# mc33063a-led-cc-driver-mk-1_0.net
KiCad netlist of a schematic drawn in EAGLE
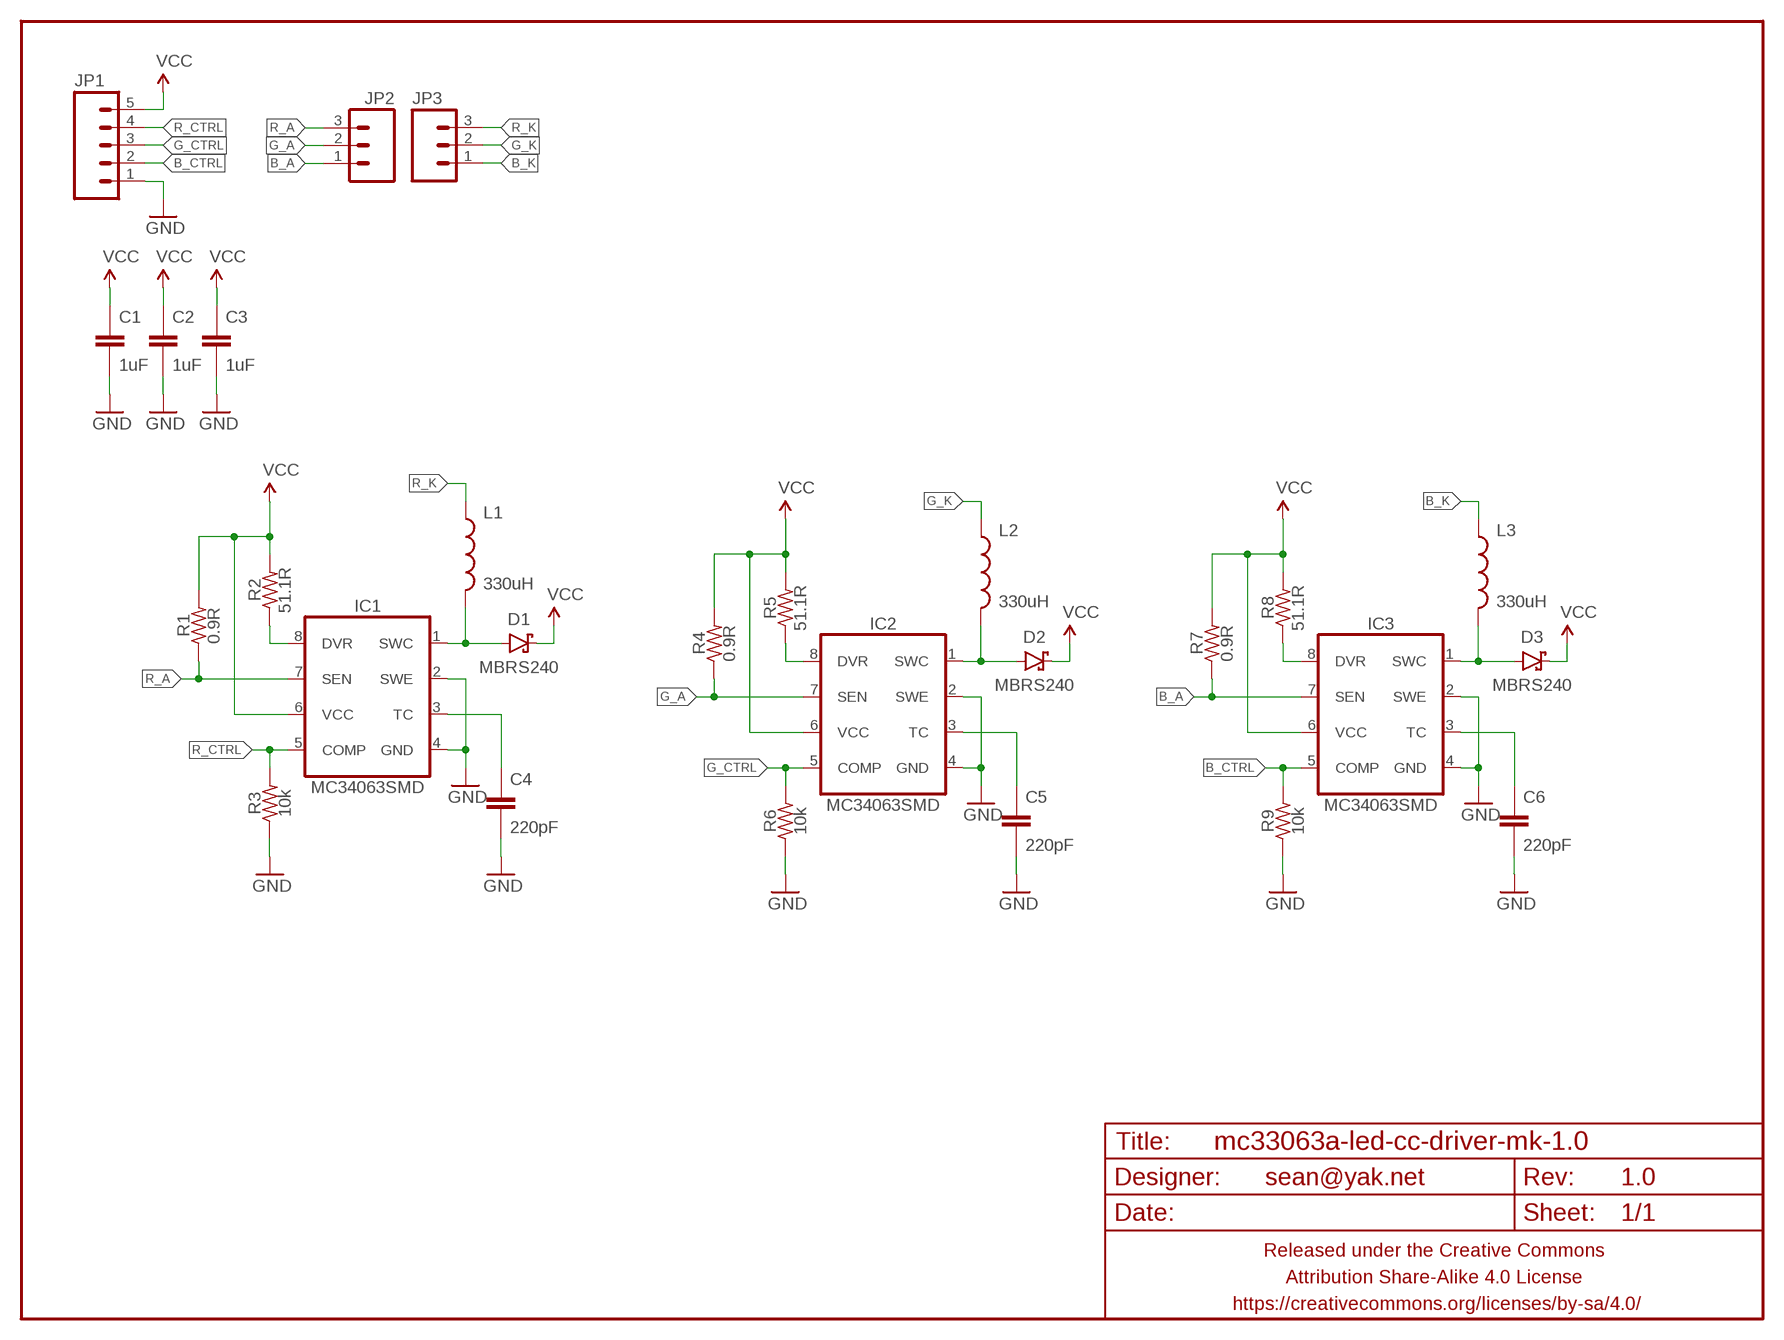
[diagram p0: schematic, sheet 1]

(export (version "E")
  (design (tool "Eeschema 10.0.6"))
  (components
    (comp (ref "C1")
      (value "1uF")
      (footprint "eagle-import:C0805")
      (libsource (lib "eagle-import") (part "CAPACITOR-CERAMICC0805"))
    )
    (comp (ref "C2")
      (value "1uF")
      (footprint "eagle-import:C0805")
      (libsource (lib "eagle-import") (part "CAPACITOR-CERAMICC0805"))
    )
    (comp (ref "C3")
      (value "1uF")
      (footprint "eagle-import:C0805")
      (libsource (lib "eagle-import") (part "CAPACITOR-CERAMICC0805"))
    )
    (comp (ref "C4")
      (value "220pF")
      (footprint "eagle-import:C0805")
      (libsource (lib "eagle-import") (part "CAPACITOR-CERAMICC0805"))
    )
    (comp (ref "C5")
      (value "220pF")
      (footprint "eagle-import:C0805")
      (libsource (lib "eagle-import") (part "CAPACITOR-CERAMICC0805"))
    )
    (comp (ref "C6")
      (value "220pF")
      (footprint "eagle-import:C0805")
      (libsource (lib "eagle-import") (part "CAPACITOR-CERAMICC0805"))
    )
    (comp (ref "D1")
      (value "MBRS240")
      (footprint "eagle-import:SMA-DIODE-SCHOTTKY")
      (libsource (lib "eagle-import") (part "DIODE-SCHOTTKYSMA"))
    )
    (comp (ref "D2")
      (value "MBRS240")
      (footprint "eagle-import:SMA-DIODE-SCHOTTKY")
      (libsource (lib "eagle-import") (part "DIODE-SCHOTTKYSMA"))
    )
    (comp (ref "D3")
      (value "MBRS240")
      (footprint "eagle-import:SMA-DIODE-SCHOTTKY")
      (libsource (lib "eagle-import") (part "DIODE-SCHOTTKYSMA"))
    )
    (comp (ref "FRAME1")
      (value "FRAME-LETTERNO_PACKAGE")
      (footprint "eagle-import:DUMMY")
      (fields (field (name "DESIGNER") "sean@yak.net") (field (name "VERSION") "1.0"))
      (libsource (lib "eagle-import") (part "FRAME-LETTERNO_PACKAGE"))
    )
    (comp (ref "IC1")
      (value "MC34063SMD")
      (footprint "eagle-import:SO08")
      (libsource (lib "eagle-import") (part "MC34063SMD"))
    )
    (comp (ref "IC2")
      (value "MC34063SMD")
      (footprint "eagle-import:SO08")
      (libsource (lib "eagle-import") (part "MC34063SMD"))
    )
    (comp (ref "IC3")
      (value "MC34063SMD")
      (footprint "eagle-import:SO08")
      (libsource (lib "eagle-import") (part "MC34063SMD"))
    )
    (comp (ref "JP1")
      (value "M05PTH")
      (footprint "eagle-import:1X05")
      (libsource (lib "eagle-import") (part "M05PTH"))
    )
    (comp (ref "JP2")
      (value "M03PTH")
      (footprint "eagle-import:1X03")
      (libsource (lib "eagle-import") (part "M03PTH"))
    )
    (comp (ref "JP3")
      (value "M03PTH")
      (footprint "eagle-import:1X03")
      (libsource (lib "eagle-import") (part "M03PTH"))
    )
    (comp (ref "L1")
      (value "330uH")
      (footprint "eagle-import:SRN8040")
      (libsource (lib "eagle-import") (part "INDUCTORSRN8040"))
    )
    (comp (ref "L2")
      (value "330uH")
      (footprint "eagle-import:SRN8040")
      (libsource (lib "eagle-import") (part "INDUCTORSRN8040"))
    )
    (comp (ref "L3")
      (value "330uH")
      (footprint "eagle-import:SRN8040")
      (libsource (lib "eagle-import") (part "INDUCTORSRN8040"))
    )
    (comp (ref "R1")
      (value "0.9R")
      (footprint "eagle-import:R2010")
      (libsource (lib "eagle-import") (part "RESISTORR2010"))
    )
    (comp (ref "R2")
      (value "51.1R")
      (footprint "eagle-import:R1206")
      (libsource (lib "eagle-import") (part "RESISTORR1206"))
    )
    (comp (ref "R3")
      (value "10k")
      (footprint "eagle-import:R0805")
      (libsource (lib "eagle-import") (part "RESISTORR0805"))
    )
    (comp (ref "R4")
      (value "0.9R")
      (footprint "eagle-import:R2010")
      (libsource (lib "eagle-import") (part "RESISTORR2010"))
    )
    (comp (ref "R5")
      (value "51.1R")
      (footprint "eagle-import:R1206")
      (libsource (lib "eagle-import") (part "RESISTORR1206"))
    )
    (comp (ref "R6")
      (value "10k")
      (footprint "eagle-import:R0805")
      (libsource (lib "eagle-import") (part "RESISTORR0805"))
    )
    (comp (ref "R7")
      (value "0.9R")
      (footprint "eagle-import:R2010")
      (libsource (lib "eagle-import") (part "RESISTORR2010"))
    )
    (comp (ref "R8")
      (value "51.1R")
      (footprint "eagle-import:R1206")
      (libsource (lib "eagle-import") (part "RESISTORR1206"))
    )
    (comp (ref "R9")
      (value "10k")
      (footprint "eagle-import:R0805")
      (libsource (lib "eagle-import") (part "RESISTORR0805"))
    )
  )
  (nets
    (net (code "1") (name "B_A") (class "Default")
      (node (ref "IC3") (pin "7") (pinfunction "SEN_7") (pintype "bidirectional"))
      (node (ref "JP2") (pin "1") (pinfunction "1_1") (pintype "passive"))
      (node (ref "R7") (pin "1") (pinfunction "1_1") (pintype "passive"))
    )
    (net (code "2") (name "B_CTRL") (class "Default")
      (node (ref "IC3") (pin "5") (pinfunction "COMP_5") (pintype "bidirectional"))
      (node (ref "JP1") (pin "2") (pinfunction "2_2") (pintype "passive"))
      (node (ref "R9") (pin "2") (pinfunction "2_2") (pintype "passive"))
    )
    (net (code "3") (name "B_K") (class "Default")
      (node (ref "JP3") (pin "1") (pinfunction "1_1") (pintype "passive"))
      (node (ref "L3") (pin "1") (pinfunction "1_1") (pintype "passive"))
    )
    (net (code "4") (name "GND") (class "Default")
      (node (ref "C1") (pin "2") (pinfunction "2_2") (pintype "passive"))
      (node (ref "C2") (pin "2") (pinfunction "2_2") (pintype "passive"))
      (node (ref "C3") (pin "2") (pinfunction "2_2") (pintype "passive"))
      (node (ref "C4") (pin "2") (pinfunction "2_2") (pintype "passive"))
      (node (ref "C5") (pin "2") (pinfunction "2_2") (pintype "passive"))
      (node (ref "C6") (pin "2") (pinfunction "2_2") (pintype "passive"))
      (node (ref "IC1") (pin "2") (pinfunction "SWE_2") (pintype "bidirectional"))
      (node (ref "IC1") (pin "4") (pinfunction "GND_4") (pintype "bidirectional"))
      (node (ref "IC2") (pin "2") (pinfunction "SWE_2") (pintype "bidirectional"))
      (node (ref "IC2") (pin "4") (pinfunction "GND_4") (pintype "bidirectional"))
      (node (ref "IC3") (pin "2") (pinfunction "SWE_2") (pintype "bidirectional"))
      (node (ref "IC3") (pin "4") (pinfunction "GND_4") (pintype "bidirectional"))
      (node (ref "JP1") (pin "1") (pinfunction "1_1") (pintype "passive"))
      (node (ref "R3") (pin "1") (pinfunction "1_1") (pintype "passive"))
      (node (ref "R6") (pin "1") (pinfunction "1_1") (pintype "passive"))
      (node (ref "R9") (pin "1") (pinfunction "1_1") (pintype "passive"))
    )
    (net (code "5") (name "G_A") (class "Default")
      (node (ref "IC2") (pin "7") (pinfunction "SEN_7") (pintype "bidirectional"))
      (node (ref "JP2") (pin "2") (pinfunction "2_2") (pintype "passive"))
      (node (ref "R4") (pin "1") (pinfunction "1_1") (pintype "passive"))
    )
    (net (code "6") (name "G_CTRL") (class "Default")
      (node (ref "IC2") (pin "5") (pinfunction "COMP_5") (pintype "bidirectional"))
      (node (ref "JP1") (pin "3") (pinfunction "3_3") (pintype "passive"))
      (node (ref "R6") (pin "2") (pinfunction "2_2") (pintype "passive"))
    )
    (net (code "7") (name "G_K") (class "Default")
      (node (ref "JP3") (pin "2") (pinfunction "2_2") (pintype "passive"))
      (node (ref "L2") (pin "1") (pinfunction "1_1") (pintype "passive"))
    )
    (net (code "8") (name "Net-(IC1-DVR)") (class "Default")
      (node (ref "IC1") (pin "8") (pinfunction "DVR_8") (pintype "bidirectional"))
      (node (ref "R2") (pin "1") (pinfunction "1_1") (pintype "passive"))
    )
    (net (code "9") (name "Net-(IC1-SWC)") (class "Default")
      (node (ref "D1") (pin "A") (pinfunction "A_A") (pintype "passive"))
      (node (ref "IC1") (pin "1") (pinfunction "SWC_1") (pintype "bidirectional"))
      (node (ref "L1") (pin "2") (pinfunction "2_2") (pintype "passive"))
    )
    (net (code "10") (name "Net-(IC1-TC)") (class "Default")
      (node (ref "C4") (pin "1") (pinfunction "1_1") (pintype "passive"))
      (node (ref "IC1") (pin "3") (pinfunction "TC_3") (pintype "bidirectional"))
    )
    (net (code "11") (name "Net-(IC2-DVR)") (class "Default")
      (node (ref "IC2") (pin "8") (pinfunction "DVR_8") (pintype "bidirectional"))
      (node (ref "R5") (pin "1") (pinfunction "1_1") (pintype "passive"))
    )
    (net (code "12") (name "Net-(IC2-SWC)") (class "Default")
      (node (ref "D2") (pin "A") (pinfunction "A_A") (pintype "passive"))
      (node (ref "IC2") (pin "1") (pinfunction "SWC_1") (pintype "bidirectional"))
      (node (ref "L2") (pin "2") (pinfunction "2_2") (pintype "passive"))
    )
    (net (code "13") (name "Net-(IC2-TC)") (class "Default")
      (node (ref "C5") (pin "1") (pinfunction "1_1") (pintype "passive"))
      (node (ref "IC2") (pin "3") (pinfunction "TC_3") (pintype "bidirectional"))
    )
    (net (code "14") (name "Net-(IC3-DVR)") (class "Default")
      (node (ref "IC3") (pin "8") (pinfunction "DVR_8") (pintype "bidirectional"))
      (node (ref "R8") (pin "1") (pinfunction "1_1") (pintype "passive"))
    )
    (net (code "15") (name "Net-(IC3-SWC)") (class "Default")
      (node (ref "D3") (pin "A") (pinfunction "A_A") (pintype "passive"))
      (node (ref "IC3") (pin "1") (pinfunction "SWC_1") (pintype "bidirectional"))
      (node (ref "L3") (pin "2") (pinfunction "2_2") (pintype "passive"))
    )
    (net (code "16") (name "Net-(IC3-TC)") (class "Default")
      (node (ref "C6") (pin "1") (pinfunction "1_1") (pintype "passive"))
      (node (ref "IC3") (pin "3") (pinfunction "TC_3") (pintype "bidirectional"))
    )
    (net (code "17") (name "R_A") (class "Default")
      (node (ref "IC1") (pin "7") (pinfunction "SEN_7") (pintype "bidirectional"))
      (node (ref "JP2") (pin "3") (pinfunction "3_3") (pintype "passive"))
      (node (ref "R1") (pin "1") (pinfunction "1_1") (pintype "passive"))
    )
    (net (code "18") (name "R_CTRL") (class "Default")
      (node (ref "IC1") (pin "5") (pinfunction "COMP_5") (pintype "bidirectional"))
      (node (ref "JP1") (pin "4") (pinfunction "4_4") (pintype "passive"))
      (node (ref "R3") (pin "2") (pinfunction "2_2") (pintype "passive"))
    )
    (net (code "19") (name "R_K") (class "Default")
      (node (ref "JP3") (pin "3") (pinfunction "3_3") (pintype "passive"))
      (node (ref "L1") (pin "1") (pinfunction "1_1") (pintype "passive"))
    )
    (net (code "20") (name "VCC") (class "Default")
      (node (ref "C1") (pin "1") (pinfunction "1_1") (pintype "passive"))
      (node (ref "C2") (pin "1") (pinfunction "1_1") (pintype "passive"))
      (node (ref "C3") (pin "1") (pinfunction "1_1") (pintype "passive"))
      (node (ref "D1") (pin "C") (pinfunction "C_C") (pintype "passive"))
      (node (ref "D2") (pin "C") (pinfunction "C_C") (pintype "passive"))
      (node (ref "D3") (pin "C") (pinfunction "C_C") (pintype "passive"))
      (node (ref "IC1") (pin "6") (pinfunction "VCC_6") (pintype "bidirectional"))
      (node (ref "IC2") (pin "6") (pinfunction "VCC_6") (pintype "bidirectional"))
      (node (ref "IC3") (pin "6") (pinfunction "VCC_6") (pintype "bidirectional"))
      (node (ref "JP1") (pin "5") (pinfunction "5_5") (pintype "passive"))
      (node (ref "R1") (pin "2") (pinfunction "2_2") (pintype "passive"))
      (node (ref "R2") (pin "2") (pinfunction "2_2") (pintype "passive"))
      (node (ref "R4") (pin "2") (pinfunction "2_2") (pintype "passive"))
      (node (ref "R5") (pin "2") (pinfunction "2_2") (pintype "passive"))
      (node (ref "R7") (pin "2") (pinfunction "2_2") (pintype "passive"))
      (node (ref "R8") (pin "2") (pinfunction "2_2") (pintype "passive"))
    )
  )
)
